# SCH_Probador-de-continuidad-con-NE-555_2.net
KiCad netlist of a schematic drawn in EasyEDA
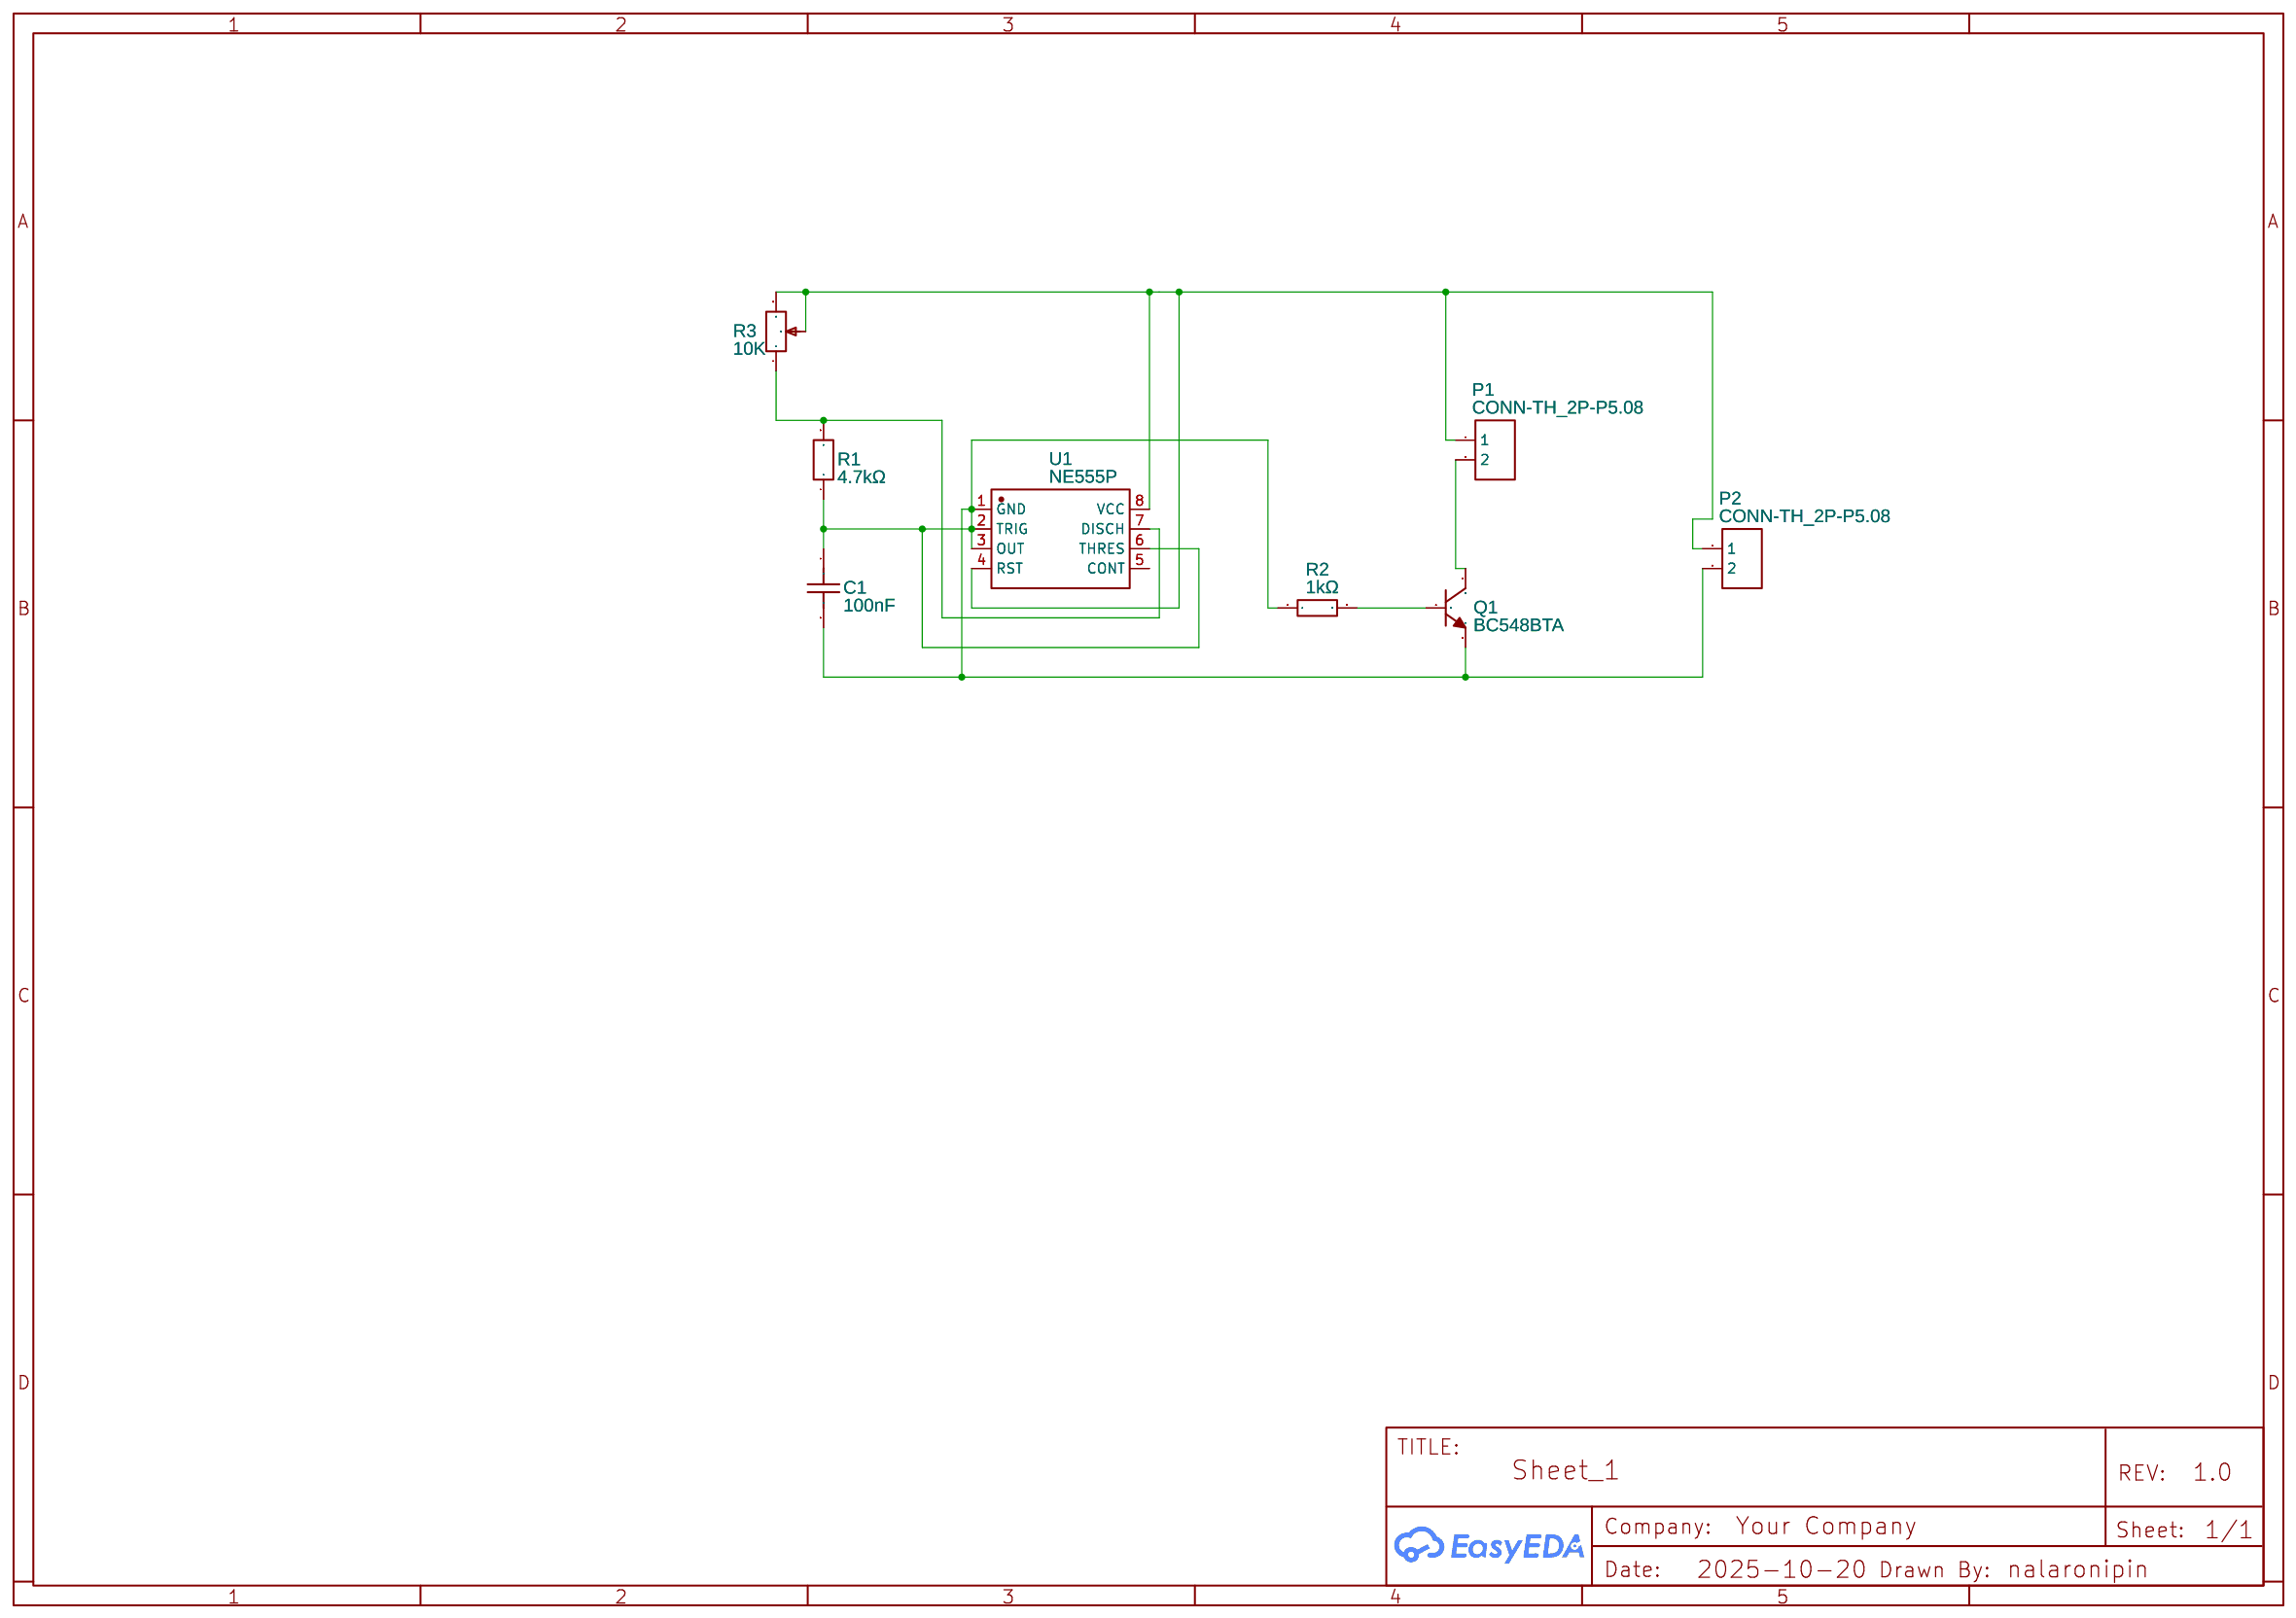
[diagram p0: schematic sheet]

(export (version "E")
  (design (tool "Eeschema 10.0.6"))
  (components
    (comp (ref "C1")
      (value "100nF")
      (fields (field (name "Manufacturer Part") "0402X104M250CT") (field (name "Manufacturer") "Walsin(华新科)"))
      (libsource (lib "") (part "0402X104M250CT"))
    )
    (comp (ref "P1") (value "CONN-TH_2P-P5.08") (libsource (lib "") (part "CONN-TH_2P-P5.08")))
    (comp (ref "P2") (value "CONN-TH_2P-P5.08") (libsource (lib "") (part "CONN-TH_2P-P5.08")))
    (comp (ref "Q1")
      (value "BC548BTA")
      (fields (field (name "Manufacturer") "onsemi(安森美)"))
      (libsource (lib "") (part "BC548BTA"))
    )
    (comp (ref "R1")
      (value "4.7kΩ")
      (fields
        (field (name "Manufacturer Part") "RD 1/4W 4K7 J T/B A1")
        (field (name "Manufacturer") "Tyohm(幸亚电阻)")
      )
      (libsource (lib "") (part "RD 1/4W 4K7 J T/B A1"))
    )
    (comp (ref "R2")
      (value "1kΩ")
      (fields (field (name "Manufacturer Part") "0402 ±5% 1K") (field (name "Manufacturer") "VO(翔胜)"))
      (libsource (lib "") (part "0402 ±5% 1K"))
    )
    (comp (ref "R3")
      (value "10K")
      (fields (field (name "Manufacturer Part") "RK097111080J") (field (name "Manufacturer") "ALPS"))
      (libsource (lib "") (part "10kpotenc"))
    )
    (comp (ref "U1")
      (value "NE555P")
      (fields (field (name "Manufacturer") "TI(德州仪器)"))
      (libsource (lib "") (part "NE555P"))
    )
  )
  (nets
    (net (code "1") (name "Net-(Q1-B)") (class "Default")
      (node (ref "Q1") (pin "2") (pinfunction "B_2") (pintype "input"))
      (node (ref "R2") (pin "2") (pinfunction "2_2") (pintype "unspecified"))
    )
    (net (code "2") (name "Net-(Q1-C)") (class "Default")
      (node (ref "P1") (pin "2") (pinfunction "2_2") (pintype "unspecified"))
      (node (ref "Q1") (pin "1") (pinfunction "C_1") (pintype "input"))
    )
    (net (code "3") (name "Net-(Q1-E)") (class "Default")
      (node (ref "C1") (pin "1") (pinfunction "1_1") (pintype "unspecified"))
      (node (ref "C1") (pin "2") (pinfunction "2_2") (pintype "unspecified"))
      (node (ref "P2") (pin "2") (pinfunction "2_2") (pintype "unspecified"))
      (node (ref "Q1") (pin "3") (pinfunction "E_3") (pintype "input"))
      (node (ref "R1") (pin "1") (pinfunction "1_1") (pintype "unspecified"))
      (node (ref "R2") (pin "1") (pinfunction "1_1") (pintype "unspecified"))
      (node (ref "U1") (pin "1") (pinfunction "GND_1") (pintype "unspecified"))
      (node (ref "U1") (pin "2") (pinfunction "TRIG_2") (pintype "unspecified"))
      (node (ref "U1") (pin "3") (pinfunction "OUT_3") (pintype "unspecified"))
      (node (ref "U1") (pin "6") (pinfunction "THRES_6") (pintype "unspecified"))
    )
    (net (code "4") (name "Net-(U1-DISCH)") (class "Default")
      (node (ref "R1") (pin "2") (pinfunction "2_2") (pintype "unspecified"))
      (node (ref "R3") (pin "1") (pinfunction "1_1") (pintype "input"))
      (node (ref "U1") (pin "7") (pinfunction "DISCH_7") (pintype "unspecified"))
    )
    (net (code "5") (name "Net-(U1-RST)") (class "Default")
      (node (ref "P1") (pin "1") (pinfunction "1_1") (pintype "unspecified"))
      (node (ref "P2") (pin "1") (pinfunction "1_1") (pintype "unspecified"))
      (node (ref "R3") (pin "2") (pinfunction "2_2") (pintype "input"))
      (node (ref "R3") (pin "3") (pinfunction "3_3") (pintype "input"))
      (node (ref "U1") (pin "4") (pinfunction "RST_4") (pintype "unspecified"))
      (node (ref "U1") (pin "8") (pinfunction "VCC_8") (pintype "unspecified"))
    )
    (net (code "6") (name "unconnected-(U1-CONT-Pad5)") (class "Default")
      (node (ref "U1") (pin "5") (pinfunction "CONT_5") (pintype "unspecified"))
    )
  )
)
